# microrelayblock_rev1.net
KiCad netlist of a schematic drawn in EAGLE
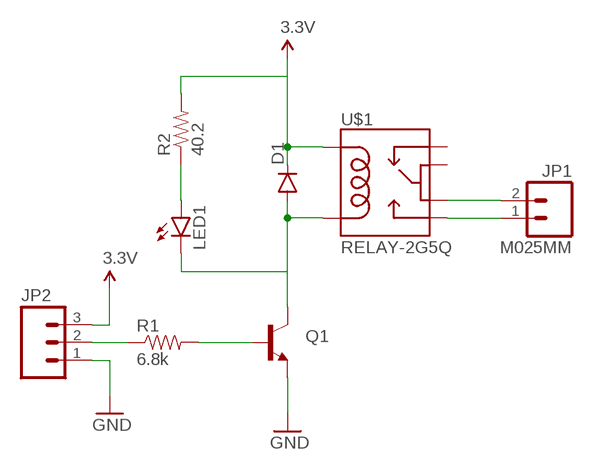
[diagram p0: schematic, sheet 1]

(export (version "E")
  (design (tool "Eeschema 10.0.6"))
  (components
    (comp (ref "D1")
      (value "DIODESMA-KIT")
      (footprint "eagle-import:SMA-DIODE-KIT")
      (libsource (lib "eagle-import") (part "DIODESMA-KIT"))
    )
    (comp (ref "JP1")
      (value "M025MM")
      (footprint "eagle-import:SCREWTERMINAL-5MM-2")
      (libsource (lib "eagle-import") (part "M025MM"))
    )
    (comp (ref "JP2")
      (value "M03SCREW")
      (footprint "eagle-import:SCREWTERMINAL-3.5MM-3")
      (libsource (lib "eagle-import") (part "M03SCREW"))
    )
    (comp (ref "LED1")
      (value "LED0603")
      (footprint "eagle-import:LED-0603")
      (libsource (lib "eagle-import") (part "LED0603"))
    )
    (comp (ref "Q1")
      (value "TRANSISTOR_NPNSOT23")
      (footprint "eagle-import:SOT23")
      (libsource (lib "eagle-import") (part "TRANSISTOR_NPNSOT23"))
    )
    (comp (ref "R1")
      (value "6.8k")
      (footprint "eagle-import:0805")
      (libsource (lib "eagle-import") (part "RESISTOR0805-RES"))
    )
    (comp (ref "R2")
      (value "40.2")
      (footprint "eagle-import:0805")
      (libsource (lib "eagle-import") (part "RESISTOR0805-RES"))
    )
    (comp (ref "U$1")
      (value "RELAY-2G5Q")
      (footprint "eagle-import:RELAY-G5V")
      (libsource (lib "eagle-import") (part "RELAY-2G5Q"))
    )
  )
  (nets
    (net (code "1") (name "3.3V") (class "Default")
      (node (ref "D1") (pin "C") (pinfunction "C_C") (pintype "passive"))
      (node (ref "JP2") (pin "3") (pinfunction "3_3") (pintype "passive"))
      (node (ref "R2") (pin "2") (pinfunction "2_2") (pintype "passive"))
      (node (ref "U$1") (pin "2") (pinfunction "2_2") (pintype "bidirectional"))
    )
    (net (code "2") (name "GND") (class "Default")
      (node (ref "JP2") (pin "1") (pinfunction "1_1") (pintype "passive"))
      (node (ref "Q1") (pin "2") (pinfunction "E_2") (pintype "passive"))
    )
    (net (code "3") (name "Net-(JP1-Pad1)") (class "Default")
      (node (ref "JP1") (pin "1") (pinfunction "1_1") (pintype "passive"))
      (node (ref "U$1") (pin "10") (pinfunction "10_10") (pintype "bidirectional"))
    )
    (net (code "4") (name "Net-(JP1-Pad2)") (class "Default")
      (node (ref "JP1") (pin "2") (pinfunction "2_2") (pintype "passive"))
      (node (ref "U$1") (pin "6") (pinfunction "6_6") (pintype "bidirectional"))
    )
    (net (code "5") (name "Net-(JP2-Pad2)") (class "Default")
      (node (ref "JP2") (pin "2") (pinfunction "2_2") (pintype "passive"))
      (node (ref "R1") (pin "1") (pinfunction "1_1") (pintype "passive"))
    )
    (net (code "6") (name "Net-(LED1-PadA)") (class "Default")
      (node (ref "LED1") (pin "A") (pinfunction "A_A") (pintype "passive"))
      (node (ref "R2") (pin "1") (pinfunction "1_1") (pintype "passive"))
    )
    (net (code "7") (name "Net-(Q1-B)") (class "Default")
      (node (ref "Q1") (pin "1") (pinfunction "B_1") (pintype "passive"))
      (node (ref "R1") (pin "2") (pinfunction "2_2") (pintype "passive"))
    )
    (net (code "8") (name "Net-(Q1-C)") (class "Default")
      (node (ref "D1") (pin "A") (pinfunction "A_A") (pintype "passive"))
      (node (ref "LED1") (pin "C") (pinfunction "C_C") (pintype "passive"))
      (node (ref "Q1") (pin "3") (pinfunction "C_3") (pintype "passive"))
      (node (ref "U$1") (pin "9") (pinfunction "9_9") (pintype "bidirectional"))
    )
    (net (code "9") (name "unconnected-(U$1-Pad1)") (class "Default")
      (node (ref "U$1") (pin "1") (pinfunction "1_1") (pintype "bidirectional"))
    )
    (net (code "10") (name "unconnected-(U$1-Pad5)") (class "Default")
      (node (ref "U$1") (pin "5") (pinfunction "5_5") (pintype "bidirectional"))
    )
  )
)
